# Qwiic_Multi_Distance_Sensor_-_VL53L3CX.net
KiCad netlist of a schematic drawn in EAGLE
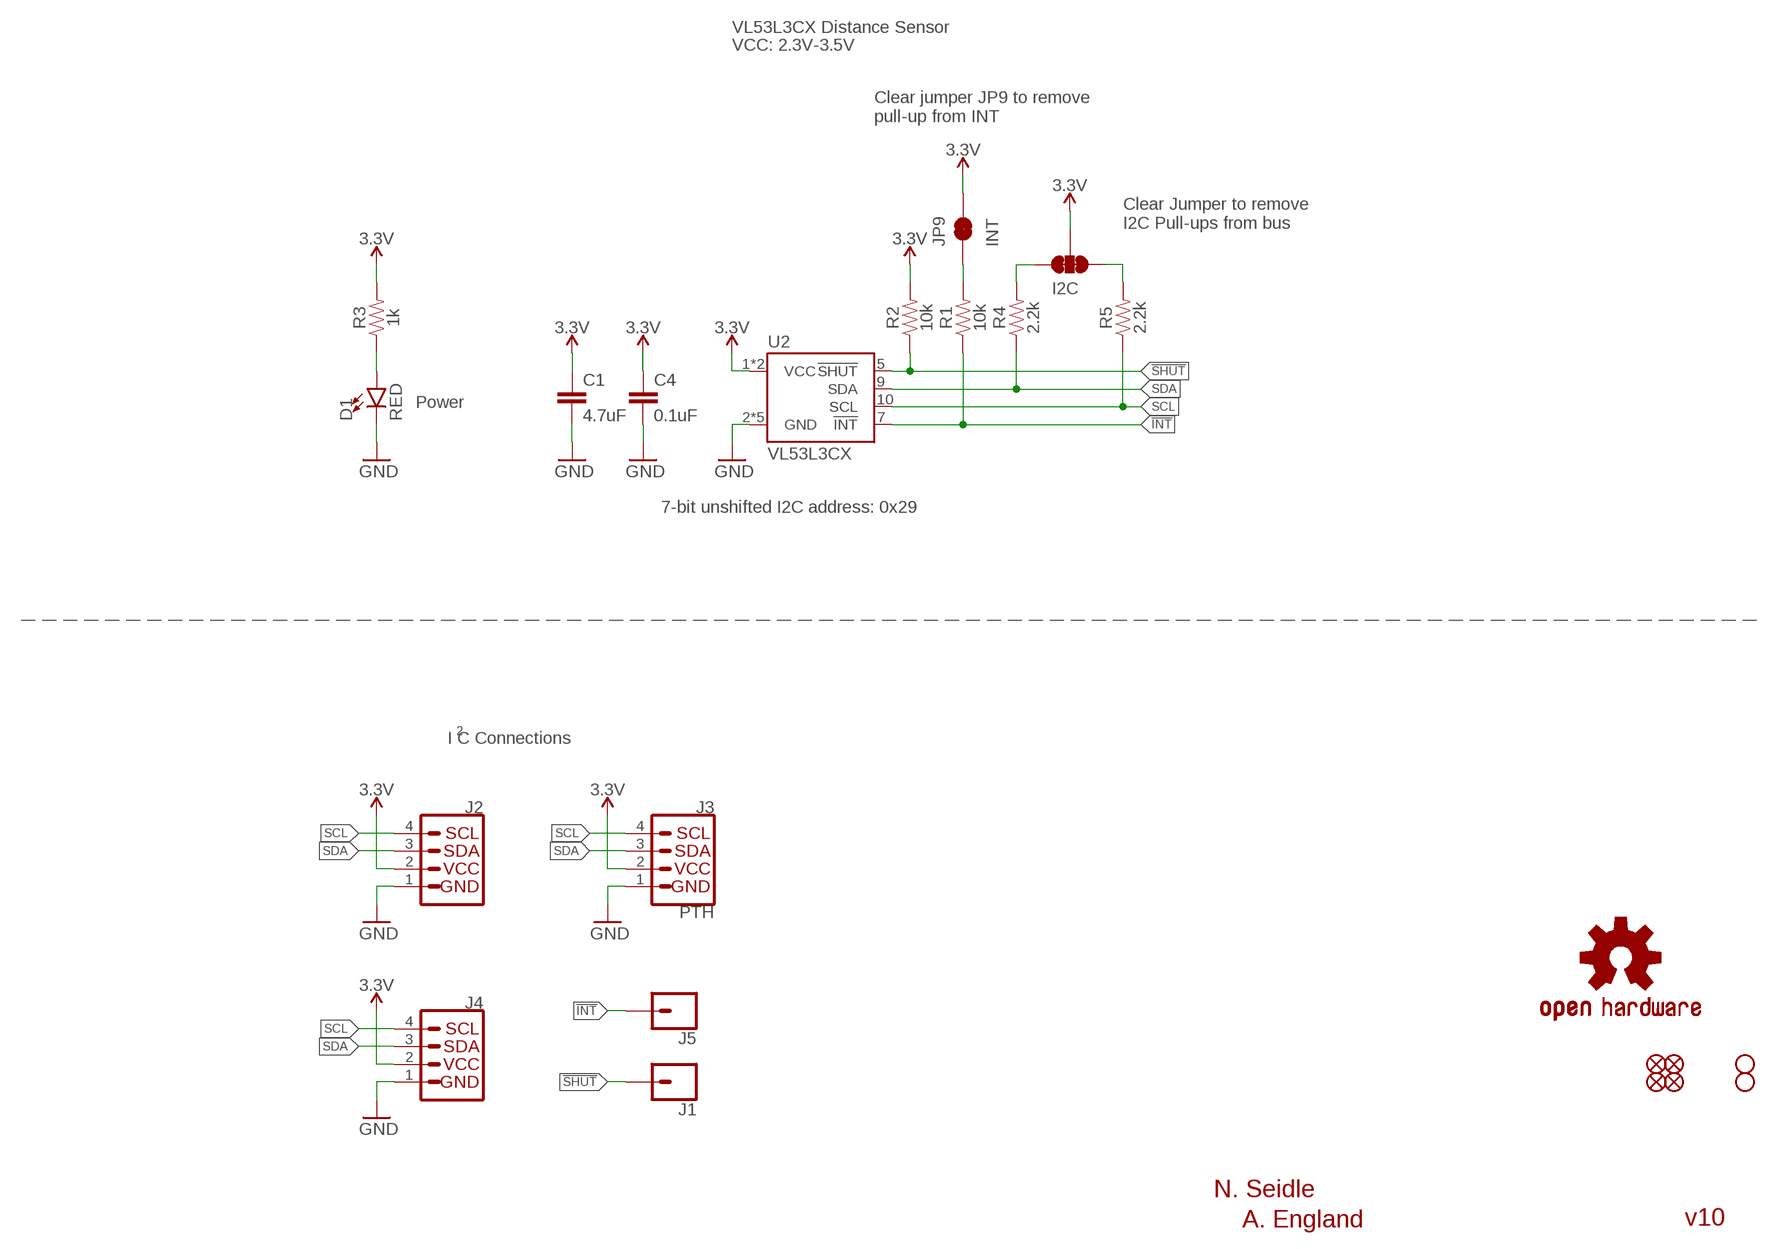
[diagram p0: schematic, sheet 1]

(export (version "E")
  (design (tool "Eeschema 10.0.6"))
  (components
    (comp (ref "C1")
      (value "4.7uF")
      (footprint "eagle-import:0603")
      (libsource (lib "eagle-import") (part "4.7UF0603"))
    )
    (comp (ref "C4")
      (value "0.1uF")
      (footprint "eagle-import:0603")
      (libsource (lib "eagle-import") (part "0.1UF-0603-25V-(+80/-20%)"))
    )
    (comp (ref "D1")
      (value "RED")
      (footprint "eagle-import:LED-0603")
      (libsource (lib "eagle-import") (part "LED-RED0603"))
    )
    (comp (ref "I2C")
      (value "JUMPER-SMT_3_2-NC_TRACE_SILK")
      (footprint "eagle-import:SMT-JUMPER_3_2-NC_TRACE_SILK")
      (libsource (lib "eagle-import") (part "JUMPER-SMT_3_2-NC_TRACE_SILK"))
    )
    (comp (ref "J1")
      (value "CONN_01PTH_NO_SILK_YES_STOP")
      (footprint "eagle-import:1X01_NO_SILK")
      (libsource (lib "eagle-import") (part "CONN_01PTH_NO_SILK_YES_STOP"))
    )
    (comp (ref "J2")
      (value "QWIIC_CONNECTORJS-1MM")
      (footprint "eagle-import:1X04_1MM_RA")
      (libsource (lib "eagle-import") (part "QWIIC_CONNECTORJS-1MM"))
    )
    (comp (ref "J3")
      (value "PTH")
      (footprint "eagle-import:1X04_NO_SILK")
      (libsource (lib "eagle-import") (part "I2C_STANDARD_NO_SILK"))
    )
    (comp (ref "J4")
      (value "QWIIC_CONNECTORJS-1MM")
      (footprint "eagle-import:1X04_1MM_RA")
      (libsource (lib "eagle-import") (part "QWIIC_CONNECTORJS-1MM"))
    )
    (comp (ref "J5")
      (value "CONN_01PTH_NO_SILK_YES_STOP")
      (footprint "eagle-import:1X01_NO_SILK")
      (libsource (lib "eagle-import") (part "CONN_01PTH_NO_SILK_YES_STOP"))
    )
    (comp (ref "JP1")
      (value "FIDUCIALUFIDUCIAL")
      (footprint "eagle-import:MICRO-FIDUCIAL")
      (libsource (lib "eagle-import") (part "FIDUCIALUFIDUCIAL"))
    )
    (comp (ref "JP2")
      (value "FIDUCIALUFIDUCIAL")
      (footprint "eagle-import:MICRO-FIDUCIAL")
      (libsource (lib "eagle-import") (part "FIDUCIALUFIDUCIAL"))
    )
    (comp (ref "JP3")
      (value "STAND-OFF")
      (footprint "eagle-import:STAND-OFF")
      (libsource (lib "eagle-import") (part "STAND-OFF"))
    )
    (comp (ref "JP4")
      (value "STAND-OFF")
      (footprint "eagle-import:STAND-OFF")
      (libsource (lib "eagle-import") (part "STAND-OFF"))
    )
    (comp (ref "JP5")
      (value "FIDUCIALUFIDUCIAL")
      (footprint "eagle-import:MICRO-FIDUCIAL")
      (libsource (lib "eagle-import") (part "FIDUCIALUFIDUCIAL"))
    )
    (comp (ref "JP6")
      (value "FIDUCIALUFIDUCIAL")
      (footprint "eagle-import:MICRO-FIDUCIAL")
      (libsource (lib "eagle-import") (part "FIDUCIALUFIDUCIAL"))
    )
    (comp (ref "JP9")
      (value "INT")
      (footprint "eagle-import:PAD-JUMPER-2-NC_BY_TRACE_YES_SILK")
      (libsource (lib "eagle-import") (part "JUMPER-PAD-2-NC_BY_TRACE"))
    )
    (comp (ref "LOGO1")
      (value "OSHW-LOGOMINI")
      (footprint "eagle-import:OSHW-LOGO-MINI")
      (libsource (lib "eagle-import") (part "OSHW-LOGOMINI"))
    )
    (comp (ref "R1")
      (value "10k")
      (footprint "eagle-import:0603")
      (libsource (lib "eagle-import") (part "10KOHM-0603-1/10W-1%"))
    )
    (comp (ref "R2")
      (value "10k")
      (footprint "eagle-import:0603")
      (libsource (lib "eagle-import") (part "10KOHM-0603-1/10W-1%"))
    )
    (comp (ref "R3")
      (value "1k")
      (footprint "eagle-import:0603")
      (libsource (lib "eagle-import") (part "1KOHM-0603-1/10W-1%"))
    )
    (comp (ref "R4")
      (value "2.2k")
      (footprint "eagle-import:0603")
      (libsource (lib "eagle-import") (part "2.2KOHM-0603-1/10W-1%"))
    )
    (comp (ref "R5")
      (value "2.2k")
      (footprint "eagle-import:0603")
      (libsource (lib "eagle-import") (part "2.2KOHM-0603-1/10W-1%"))
    )
    (comp (ref "U2")
      (value "VL53L3CX")
      (footprint "eagle-import:VL53L1X")
      (libsource (lib "eagle-import") (part "VL53L1XSMD"))
    )
  )
  (nets
    (net (code "1") (name "/~{INT}") (class "Default")
      (node (ref "J5") (pin "1") (pinfunction "1_1") (pintype "passive"))
      (node (ref "R1") (pin "1") (pinfunction "1_1") (pintype "passive"))
      (node (ref "U2") (pin "7") (pinfunction "~{INT}_7") (pintype "bidirectional"))
    )
    (net (code "2") (name "/~{SHUT}") (class "Default")
      (node (ref "J1") (pin "1") (pinfunction "1_1") (pintype "passive"))
      (node (ref "R2") (pin "1") (pinfunction "1_1") (pintype "passive"))
      (node (ref "U2") (pin "5") (pinfunction "~{SHUT}_5") (pintype "bidirectional"))
    )
    (net (code "3") (name "3.3V") (class "Default")
      (node (ref "C1") (pin "1") (pinfunction "1_1") (pintype "passive"))
      (node (ref "C4") (pin "1") (pinfunction "1_1") (pintype "passive"))
      (node (ref "I2C") (pin "2") (pinfunction "2_2") (pintype "passive"))
      (node (ref "J2") (pin "2") (pinfunction "2_2") (pintype "power_in"))
      (node (ref "J3") (pin "2") (pinfunction "VCC_2") (pintype "power_in"))
      (node (ref "J4") (pin "2") (pinfunction "2_2") (pintype "power_in"))
      (node (ref "JP9") (pin "2") (pinfunction "2_2") (pintype "passive"))
      (node (ref "R2") (pin "2") (pinfunction "2_2") (pintype "passive"))
      (node (ref "R3") (pin "2") (pinfunction "2_2") (pintype "passive"))
      (node (ref "U2") (pin "1") (pinfunction "VCC_1") (pintype "bidirectional"))
      (node (ref "U2") (pin "11") (pinfunction "VCC_11") (pintype "bidirectional"))
    )
    (net (code "4") (name "GND") (class "Default")
      (node (ref "C1") (pin "2") (pinfunction "2_2") (pintype "passive"))
      (node (ref "C4") (pin "2") (pinfunction "2_2") (pintype "passive"))
      (node (ref "D1") (pin "C") (pinfunction "C_C") (pintype "passive"))
      (node (ref "J2") (pin "1") (pinfunction "1_1") (pintype "power_in"))
      (node (ref "J3") (pin "1") (pinfunction "GND_1") (pintype "power_in"))
      (node (ref "J4") (pin "1") (pinfunction "1_1") (pintype "power_in"))
      (node (ref "U2") (pin "12") (pinfunction "GND_12") (pintype "bidirectional"))
      (node (ref "U2") (pin "2") (pinfunction "GND_2") (pintype "bidirectional"))
      (node (ref "U2") (pin "3") (pinfunction "GND_3") (pintype "bidirectional"))
      (node (ref "U2") (pin "4") (pinfunction "GND_4") (pintype "bidirectional"))
      (node (ref "U2") (pin "6") (pinfunction "GND_6") (pintype "bidirectional"))
    )
    (net (code "5") (name "Net-(D1-PadA)") (class "Default")
      (node (ref "D1") (pin "A") (pinfunction "A_A") (pintype "passive"))
      (node (ref "R3") (pin "1") (pinfunction "1_1") (pintype "passive"))
    )
    (net (code "6") (name "Net-(I2C-Pad1)") (class "Default")
      (node (ref "I2C") (pin "1") (pinfunction "1_1") (pintype "passive"))
      (node (ref "R5") (pin "2") (pinfunction "2_2") (pintype "passive"))
    )
    (net (code "7") (name "Net-(I2C-Pad3)") (class "Default")
      (node (ref "I2C") (pin "3") (pinfunction "3_3") (pintype "passive"))
      (node (ref "R4") (pin "2") (pinfunction "2_2") (pintype "passive"))
    )
    (net (code "8") (name "Net-(JP9-Pad1)") (class "Default")
      (node (ref "JP9") (pin "1") (pinfunction "1_1") (pintype "passive"))
      (node (ref "R1") (pin "2") (pinfunction "2_2") (pintype "passive"))
    )
    (net (code "9") (name "SCL") (class "Default")
      (node (ref "J2") (pin "4") (pinfunction "4_4") (pintype "passive"))
      (node (ref "J3") (pin "4") (pinfunction "SCL_4") (pintype "passive"))
      (node (ref "J4") (pin "4") (pinfunction "4_4") (pintype "passive"))
      (node (ref "R5") (pin "1") (pinfunction "1_1") (pintype "passive"))
      (node (ref "U2") (pin "10") (pinfunction "SCL_10") (pintype "bidirectional"))
    )
    (net (code "10") (name "SDA") (class "Default")
      (node (ref "J2") (pin "3") (pinfunction "3_3") (pintype "passive"))
      (node (ref "J3") (pin "3") (pinfunction "SDA_3") (pintype "passive"))
      (node (ref "J4") (pin "3") (pinfunction "3_3") (pintype "passive"))
      (node (ref "R4") (pin "1") (pinfunction "1_1") (pintype "passive"))
      (node (ref "U2") (pin "9") (pinfunction "SDA_9") (pintype "bidirectional"))
    )
  )
)
